# MotorDriver.net
KiCad netlist of a schematic drawn in Altium Designer
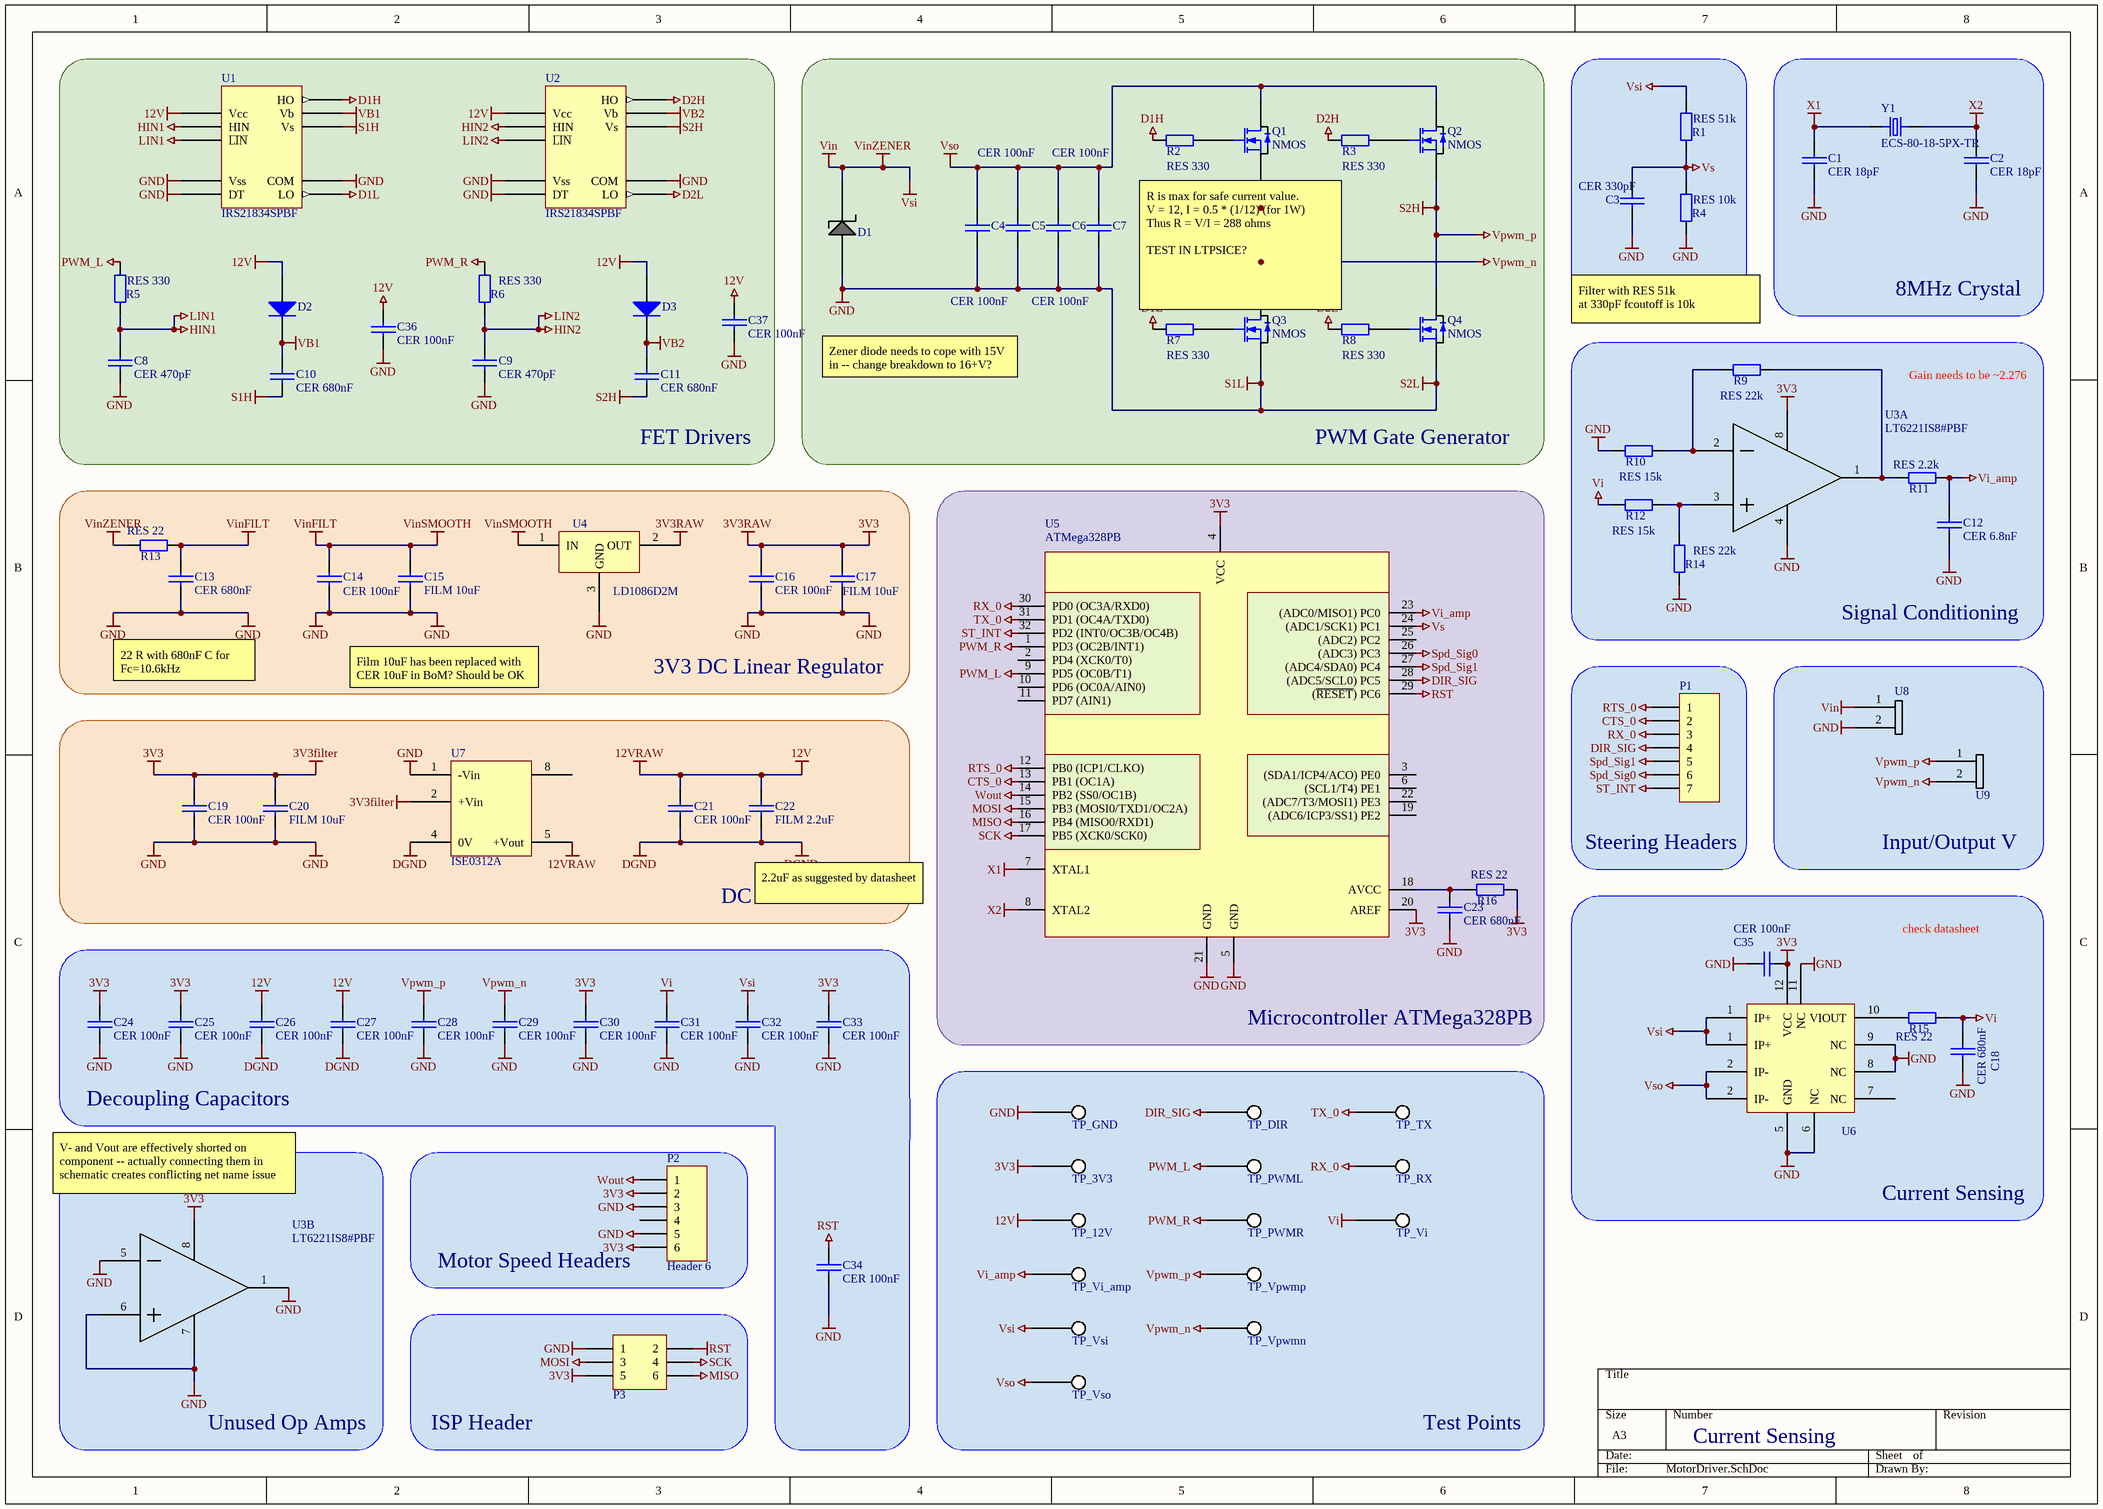
[diagram p0: MotorDriver.SchDoc]

(export (version "E")
  (design (tool "Eeschema 10.0.6"))
  (components
    (comp (ref "C1")
      (value "CER 18pF")
      (footprint "C1210")
      (description "CCAP0805")
      (fields (field (name "MPN") "?"))
      (libsource (lib "E209_Lib") (part "CCAP0805"))
    )
    (comp (ref "C2")
      (value "CER 18pF")
      (footprint "C1210")
      (description "CCAP0805")
      (fields (field (name "MPN") "?"))
      (libsource (lib "E209_Lib") (part "CCAP0805"))
    )
    (comp (ref "C3")
      (value "CER 330pF")
      (footprint "C1206")
      (description "CCAP0805")
      (fields (field (name "MPN") "?"))
      (libsource (lib "E209_Lib") (part "CCAP0805"))
    )
    (comp (ref "C4")
      (value "CER 100nF")
      (footprint "C1206")
      (description "CAP CER 0.1UF 100V C0G 1206")
      (fields (field (name "MPN") "C3216C0G2A104J160AC") (field (name "MANUFACTURER") "TDK Corporation"))
      (libsource (lib "E209_Lib") (part "Cap CER Decoup C3216C0G2A104J160AC"))
    )
    (comp (ref "C5")
      (value "CER 100nF")
      (footprint "C1206")
      (description "CAP CER 0.1UF 100V C0G 1206")
      (fields (field (name "MPN") "C3216C0G2A104J160AC") (field (name "MANUFACTURER") "TDK Corporation"))
      (libsource (lib "E209_Lib") (part "Cap CER Decoup C3216C0G2A104J160AC"))
    )
    (comp (ref "C6")
      (value "CER 100nF")
      (footprint "C1206")
      (description "CAP CER 0.1UF 100V C0G 1206")
      (fields (field (name "MPN") "C3216C0G2A104J160AC") (field (name "MANUFACTURER") "TDK Corporation"))
      (libsource (lib "E209_Lib") (part "Cap CER Decoup C3216C0G2A104J160AC"))
    )
    (comp (ref "C7")
      (value "CER 100nF")
      (footprint "C1206")
      (description "CAP CER 0.1UF 100V C0G 1206")
      (fields (field (name "MPN") "C3216C0G2A104J160AC") (field (name "MANUFACTURER") "TDK Corporation"))
      (libsource (lib "E209_Lib") (part "Cap CER Decoup C3216C0G2A104J160AC"))
    )
    (comp (ref "C8")
      (value "CER 470pF")
      (footprint "C1210")
      (description "CCAP0805")
      (fields (field (name "MPN") "?"))
      (libsource (lib "E209_Lib") (part "CCAP0805"))
    )
    (comp (ref "C9")
      (value "CER 470pF")
      (footprint "C1210")
      (description "CCAP0805")
      (fields (field (name "MPN") "?"))
      (libsource (lib "E209_Lib") (part "CCAP0805"))
    )
    (comp (ref "C10")
      (value "CER 680nF")
      (footprint "C1206")
      (description "CAP CER 0.1UF 100V C0G 1206")
      (fields (field (name "MPN") "C3216C0G2A104J160AC") (field (name "MANUFACTURER") "TDK Corporation"))
      (libsource (lib "E209_Lib") (part "Cap CER Decoup C3216C0G2A104J160AC"))
    )
    (comp (ref "C11")
      (value "CER 680nF")
      (footprint "C1206")
      (description "CAP CER 0.1UF 100V C0G 1206")
      (fields (field (name "MPN") "C3216C0G2A104J160AC") (field (name "MANUFACTURER") "TDK Corporation"))
      (libsource (lib "E209_Lib") (part "Cap CER Decoup C3216C0G2A104J160AC"))
    )
    (comp (ref "C12")
      (value "CER 6.8nF")
      (footprint "C1206")
      (description "CCAP0805")
      (fields (field (name "MPN") "?"))
      (libsource (lib "E209_Lib") (part "CCAP0805"))
    )
    (comp (ref "C13")
      (value "CER 680nF")
      (footprint "C1206")
      (description "CCAP0805")
      (fields (field (name "MPN") "?"))
      (libsource (lib "E209_Lib") (part "CCAP0805"))
    )
    (comp (ref "C14")
      (value "CER 100nF")
      (footprint "C1206")
      (description "CCAP0805")
      (fields (field (name "MPN") "?"))
      (libsource (lib "E209_Lib") (part "CCAP0805"))
    )
    (comp (ref "C15")
      (value "FILM 10uF")
      (footprint "LDECE4150KA0N00")
      (description "CAP FILM 1.5UF 10% 50VDC 2824")
      (fields (field (name "MPN") "LDECE4150KA0N00") (field (name "MANUFACTURER") "KEMET"))
      (libsource (lib "E209_Lib") (part "Cap Film SMD LDECE4150KA0N00"))
    )
    (comp (ref "C16")
      (value "CER 100nF")
      (footprint "C1206")
      (description "CAP CER 0.1UF 100V C0G 1206")
      (fields (field (name "MPN") "C3216C0G2A104J160AC") (field (name "MANUFACTURER") "TDK Corporation"))
      (libsource (lib "E209_Lib") (part "Cap CER Decoup C3216C0G2A104J160AC"))
    )
    (comp (ref "C17")
      (value "FILM 10uF")
      (footprint "LDECE4150KA0N00")
      (description "CAP FILM 1.5UF 10% 50VDC 2824")
      (fields (field (name "MPN") "LDECE4150KA0N00") (field (name "MANUFACTURER") "KEMET"))
      (libsource (lib "E209_Lib") (part "Cap Film SMD LDECE4150KA0N00"))
    )
    (comp (ref "C18")
      (value "CER 680nF")
      (footprint "C1206")
      (description "CCAP0805")
      (fields (field (name "MPN") "?"))
      (libsource (lib "E209_Lib") (part "CCAP0805"))
    )
    (comp (ref "C19")
      (value "CER 100nF")
      (footprint "C1206")
      (description "CCAP0805")
      (fields (field (name "MPN") "?"))
      (libsource (lib "E209_Lib") (part "CCAP0805"))
    )
    (comp (ref "C20")
      (value "FILM 10uF")
      (footprint "LDECE4150KA0N00")
      (description "CAP FILM 1.5UF 10% 50VDC 2824")
      (fields (field (name "MPN") "LDECE4150KA0N00") (field (name "MANUFACTURER") "KEMET"))
      (libsource (lib "E209_Lib") (part "Cap Film SMD LDECE4150KA0N00"))
    )
    (comp (ref "C21")
      (value "CER 100nF")
      (footprint "C1206")
      (description "CCAP0805")
      (fields (field (name "MPN") "?"))
      (libsource (lib "E209_Lib") (part "CCAP0805"))
    )
    (comp (ref "C22")
      (value "FILM 2.2uF")
      (footprint "LDECE4150KA0N00")
      (description "CAP FILM 1.5UF 10% 50VDC 2824")
      (fields (field (name "MPN") "LDECE4150KA0N00") (field (name "MANUFACTURER") "KEMET"))
      (libsource (lib "E209_Lib") (part "Cap Film SMD LDECE4150KA0N00"))
    )
    (comp (ref "C23")
      (value "CER 680nF")
      (footprint "C1206")
      (description "CCAP0805")
      (fields (field (name "MPN") "?"))
      (libsource (lib "E209_Lib") (part "CCAP0805"))
    )
    (comp (ref "C24")
      (value "CER 100nF")
      (footprint "C1206")
      (description "CCAP0805")
      (fields (field (name "MPN") "?"))
      (libsource (lib "E209_Lib") (part "CCAP0805"))
    )
    (comp (ref "C25")
      (value "CER 100nF")
      (footprint "C0805")
      (description "CCAP0805")
      (fields (field (name "MPN") "?"))
      (libsource (lib "E209_Lib") (part "CCAP0805"))
    )
    (comp (ref "C26")
      (value "CER 100nF")
      (footprint "C1206")
      (description "CAP CER 0.1UF 100V C0G 1206")
      (fields (field (name "MPN") "C3216C0G2A104J160AC") (field (name "MANUFACTURER") "TDK Corporation"))
      (libsource (lib "E209_Lib") (part "Cap CER Decoup C3216C0G2A104J160AC"))
    )
    (comp (ref "C27")
      (value "CER 100nF")
      (footprint "C1206")
      (description "CAP CER 0.1UF 100V C0G 1206")
      (fields (field (name "MPN") "C3216C0G2A104J160AC") (field (name "MANUFACTURER") "TDK Corporation"))
      (libsource (lib "E209_Lib") (part "Cap CER Decoup C3216C0G2A104J160AC"))
    )
    (comp (ref "C28")
      (value "CER 100nF")
      (footprint "C1206")
      (description "CCAP0805")
      (fields (field (name "MPN") "?"))
      (libsource (lib "E209_Lib") (part "CCAP0805"))
    )
    (comp (ref "C29")
      (value "CER 100nF")
      (footprint "C1206")
      (description "CCAP0805")
      (fields (field (name "MPN") "?"))
      (libsource (lib "E209_Lib") (part "CCAP0805"))
    )
    (comp (ref "C30")
      (value "CER 100nF")
      (footprint "C0805")
      (description "CCAP0805")
      (fields (field (name "MPN") "?"))
      (libsource (lib "E209_Lib") (part "CCAP0805"))
    )
    (comp (ref "C31")
      (value "CER 100nF")
      (footprint "C0805")
      (description "CCAP0805")
      (fields (field (name "MPN") "?"))
      (libsource (lib "E209_Lib") (part "CCAP0805"))
    )
    (comp (ref "C32")
      (value "CER 100nF")
      (footprint "C1206")
      (description "CCAP0805")
      (fields (field (name "MPN") "?"))
      (libsource (lib "E209_Lib") (part "CCAP0805"))
    )
    (comp (ref "C33")
      (value "CER 100nF")
      (footprint "C0805")
      (description "CCAP0805")
      (fields (field (name "MPN") "?"))
      (libsource (lib "E209_Lib") (part "CCAP0805"))
    )
    (comp (ref "C34")
      (value "CER 100nF")
      (footprint "C1206")
      (description "CCAP0805")
      (fields (field (name "MPN") "?"))
      (libsource (lib "E209_Lib") (part "CCAP0805"))
    )
    (comp (ref "C35")
      (value "CER 100nF")
      (footprint "C1206")
      (description "CCAP0805")
      (fields (field (name "MPN") "?"))
      (libsource (lib "E209_Lib") (part "CCAP0805"))
    )
    (comp (ref "C36")
      (value "CER 100nF")
      (footprint "C1206")
      (description "CAP CER 0.1UF 100V C0G 1206")
      (fields (field (name "MPN") "C3216C0G2A104J160AC") (field (name "MANUFACTURER") "TDK Corporation"))
      (libsource (lib "E209_Lib") (part "Cap CER Decoup C3216C0G2A104J160AC"))
    )
    (comp (ref "C37")
      (value "CER 100nF")
      (footprint "C1206")
      (description "CAP CER 0.1UF 100V C0G 1206")
      (fields (field (name "MPN") "C3216C0G2A104J160AC") (field (name "MANUFACTURER") "TDK Corporation"))
      (libsource (lib "E209_Lib") (part "Cap CER Decoup C3216C0G2A104J160AC"))
    )
    (comp (ref "D1")
      (value "DO-214AA SMB")
      (footprint "DO-214AA")
      (description "14V zener diode")
      (libsource (lib "SumWkshop") (part "SMBJ5351B-TP"))
    )
    (comp (ref "D2")
      (value "MSS1P6-M3/89A")
      (footprint "MicroSMP (DO-219AD)")
      (description "DIODE SCHOTTKY 60V 1A MICROSMP")
      (fields (field (name "MANUFACTURER") "Vishay Semiconductor Diodes Division"))
      (libsource (lib "E209_Lib") (part "Diode MSS1P6-M3/89A"))
    )
    (comp (ref "D3")
      (value "MSS1P6-M3/89A")
      (footprint "MicroSMP (DO-219AD)")
      (description "DIODE SCHOTTKY 60V 1A MICROSMP")
      (fields (field (name "MANUFACTURER") "Vishay Semiconductor Diodes Division"))
      (libsource (lib "E209_Lib") (part "Diode MSS1P6-M3/89A"))
    )
    (comp (ref "P1")
      (value "Header 7")
      (footprint "HDR1X7")
      (description "Header, 7-Pin")
      (fields (field (name "PUBLISHER") "Altium Limited"))
      (libsource (lib "Miscellaneous Connectors") (part "Header 7"))
    )
    (comp (ref "P2")
      (value "Header 6")
      (footprint "HDR1X6")
      (description "Header, 6-Pin")
      (fields (field (name "PUBLISHER") "Altium Limited"))
      (libsource (lib "Miscellaneous Connectors") (part "Header 6"))
    )
    (comp (ref "P3")
      (value "HDR3X2")
      (footprint "HDR2X3_2P54")
      (description "Header, 3-Pin, Dual row")
      (libsource (lib "CommonDevices_V1") (part "HDR3X2"))
    )
    (comp (ref "Q1")
      (value "NMOS")
      (footprint "BSC072N08NS5ATMA1_modified_v2")
      (description "MOSFET N-CH 80V 74A 8TDSON")
      (fields (field (name "MPN") "BSC072N08NS5ATMA1") (field (name "MANUFACTURER") "Infineon Technologies"))
      (libsource (lib "E209_Lib") (part "NMOS OptiMOS BSC072N08NS5ATMA1"))
    )
    (comp (ref "Q2")
      (value "NMOS")
      (footprint "BSC072N08NS5ATMA1_modified_v2")
      (description "MOSFET N-CH 80V 74A 8TDSON")
      (fields (field (name "MPN") "BSC072N08NS5ATMA1") (field (name "MANUFACTURER") "Infineon Technologies"))
      (libsource (lib "E209_Lib") (part "NMOS OptiMOS BSC072N08NS5ATMA1"))
    )
    (comp (ref "Q3")
      (value "NMOS")
      (footprint "BSC072N08NS5ATMA1_modified_v2")
      (description "MOSFET N-CH 80V 74A 8TDSON")
      (fields (field (name "MPN") "BSC072N08NS5ATMA1") (field (name "MANUFACTURER") "Infineon Technologies"))
      (libsource (lib "E209_Lib") (part "NMOS OptiMOS BSC072N08NS5ATMA1"))
    )
    (comp (ref "Q4")
      (value "NMOS")
      (footprint "BSC072N08NS5ATMA1_modified_v2")
      (description "MOSFET N-CH 80V 74A 8TDSON")
      (fields (field (name "MPN") "BSC072N08NS5ATMA1") (field (name "MANUFACTURER") "Infineon Technologies"))
      (libsource (lib "E209_Lib") (part "NMOS OptiMOS BSC072N08NS5ATMA1"))
    )
    (comp (ref "R1")
      (value "RES 51k")
      (footprint "R0805")
      (description "RES0805")
      (fields (field (name "MPN") "?"))
      (libsource (lib "") (part "RES0805_1"))
    )
    (comp (ref "R2")
      (value "RES 330")
      (footprint "R0805")
      (description "RES0805")
      (fields (field (name "MPN") "?"))
      (libsource (lib "E209_Lib") (part "RES0805"))
    )
    (comp (ref "R3")
      (value "RES 330")
      (footprint "R0805")
      (description "RES0805")
      (fields (field (name "MPN") "?"))
      (libsource (lib "E209_Lib") (part "RES0805"))
    )
    (comp (ref "R4")
      (value "RES 10k")
      (footprint "R0805")
      (description "RES0805")
      (fields (field (name "MPN") "?"))
      (libsource (lib "") (part "RES0805_1"))
    )
    (comp (ref "R5")
      (value "RES 330")
      (footprint "R0805")
      (description "RES0805")
      (fields (field (name "MPN") "?"))
      (libsource (lib "") (part "RES0805_1"))
    )
    (comp (ref "R6")
      (value "RES 330")
      (footprint "R0805")
      (description "RES0805")
      (fields (field (name "MPN") "?"))
      (libsource (lib "") (part "RES0805_1"))
    )
    (comp (ref "R7")
      (value "RES 330")
      (footprint "R0805")
      (description "RES0805")
      (fields (field (name "MPN") "?"))
      (libsource (lib "E209_Lib") (part "RES0805"))
    )
    (comp (ref "R8")
      (value "RES 330")
      (footprint "R0805")
      (description "RES0805")
      (fields (field (name "MPN") "?"))
      (libsource (lib "E209_Lib") (part "RES0805"))
    )
    (comp (ref "R9")
      (value "RES 22k")
      (footprint "R0805")
      (description "RES0805")
      (fields (field (name "MPN") "?"))
      (libsource (lib "E209_Lib") (part "RES0805"))
    )
    (comp (ref "R10")
      (value "RES 15k")
      (footprint "R0805")
      (description "RES0805")
      (fields (field (name "MPN") "?"))
      (libsource (lib "E209_Lib") (part "RES0805"))
    )
    (comp (ref "R11")
      (value "RES 2.2k")
      (footprint "R0805")
      (description "RES0805")
      (fields (field (name "MPN") "?"))
      (libsource (lib "") (part "RES0805_2"))
    )
    (comp (ref "R12")
      (value "RES 15k")
      (footprint "R0805")
      (description "RES0805")
      (fields (field (name "MPN") "?"))
      (libsource (lib "E209_Lib") (part "RES0805"))
    )
    (comp (ref "R13")
      (value "RES 22")
      (footprint "R0805")
      (description "RES0805")
      (fields (field (name "MPN") "?"))
      (libsource (lib "E209_Lib") (part "RES0805"))
    )
    (comp (ref "R14")
      (value "RES 22k")
      (footprint "R0805")
      (description "RES0805")
      (fields (field (name "MPN") "?"))
      (libsource (lib "") (part "RES0805_1"))
    )
    (comp (ref "R15")
      (value "RES 22")
      (footprint "R0805")
      (description "RES0805")
      (fields (field (name "MPN") "?"))
      (libsource (lib "E209_Lib") (part "RES0805"))
    )
    (comp (ref "R16")
      (value "RES 22")
      (footprint "R0805")
      (description "RES0805")
      (fields (field (name "MPN") "?"))
      (libsource (lib "E209_Lib") (part "RES0805"))
    )
    (comp (ref "TP_3V3")
      (value "TP_3V3")
      (footprint "TP5015")
      (description "SM Test Point 5015")
      (libsource (lib "SumWkshop") (part "TP_5015"))
    )
    (comp (ref "TP_12V")
      (value "TP_12V")
      (footprint "TP5015")
      (description "SM Test Point 5015")
      (libsource (lib "SumWkshop") (part "TP_5015"))
    )
    (comp (ref "TP_DIR")
      (value "TP_DIR")
      (footprint "TP5015")
      (description "SM Test Point 5015")
      (libsource (lib "SumWkshop") (part "TP_5015"))
    )
    (comp (ref "TP_GND")
      (value "TP_GND")
      (footprint "TP5015")
      (description "SM Test Point 5015")
      (libsource (lib "SumWkshop") (part "TP_5015"))
    )
    (comp (ref "TP_PWML")
      (value "TP_F/B")
      (footprint "TP5015")
      (description "SM Test Point 5015")
      (libsource (lib "SumWkshop") (part "TP_5015"))
    )
    (comp (ref "TP_PWMR")
      (value "TP_PWM")
      (footprint "TP5015")
      (description "SM Test Point 5015")
      (libsource (lib "SumWkshop") (part "TP_5015"))
    )
    (comp (ref "TP_RX")
      (value "TP_RX")
      (footprint "TP5015")
      (description "SM Test Point 5015")
      (libsource (lib "SumWkshop") (part "TP_5015"))
    )
    (comp (ref "TP_TX")
      (value "TP_TX")
      (footprint "TP5015")
      (description "SM Test Point 5015")
      (libsource (lib "SumWkshop") (part "TP_5015"))
    )
    (comp (ref "TP_Vi")
      (value "TP_Vi")
      (footprint "TP5015")
      (description "SM Test Point 5015")
      (libsource (lib "SumWkshop") (part "TP_5015"))
    )
    (comp (ref "TP_Vi_amp")
      (value "TP_Vi_amp")
      (footprint "TP5015")
      (description "SM Test Point 5015")
      (libsource (lib "SumWkshop") (part "TP_5015"))
    )
    (comp (ref "TP_Vpwmn")
      (value "TP_Vsi")
      (footprint "TP5015")
      (description "SM Test Point 5015")
      (libsource (lib "SumWkshop") (part "TP_5015"))
    )
    (comp (ref "TP_Vpwmp")
      (value "TP_Vi_amp")
      (footprint "TP5015")
      (description "SM Test Point 5015")
      (libsource (lib "SumWkshop") (part "TP_5015"))
    )
    (comp (ref "TP_Vsi")
      (value "TP_Vsi")
      (footprint "TP5015")
      (description "SM Test Point 5015")
      (libsource (lib "SumWkshop") (part "TP_5015"))
    )
    (comp (ref "TP_Vso")
      (value "TP_Vso")
      (footprint "TP5015")
      (description "SM Test Point 5015")
      (libsource (lib "SumWkshop") (part "TP_5015"))
    )
    (comp (ref "U1")
      (value "IRS21834SPBF")
      (footprint "SOIC127P600X175-14N")
      (description "IC GATE DRVR HALF-BRIDGE 14SOIC")
      (libsource (lib "SumWkshop") (part "IRS21834SPBF"))
    )
    (comp (ref "U2")
      (value "IRS21834SPBF")
      (footprint "SOIC127P600X175-14N")
      (description "IC GATE DRVR HALF-BRIDGE 14SOIC")
      (libsource (lib "SumWkshop") (part "IRS21834SPBF"))
    )
    (comp (ref "U3")
      (value "LT6221IS8#PBF")
      (footprint "SOIC8_NARROW")
      (libsource (lib "SumWkshop") (part "LT6221IS8#PBF"))
    )
    (comp (ref "U4")
      (value "LD1086D2M")
      (footprint "D2PAK-3L")
      (description "3.3V linear voltage regulator")
      (libsource (lib "SumWkshop") (part "LD1086D2M33TR"))
    )
    (comp (ref "U5")
      (value "ATMega328PB")
      (footprint "TQFP32")
      (description "IC MCU 8BIT 32KB FLASH 32TQFP")
      (libsource (lib "CommonDevices_V1") (part "ATMega328PB"))
    )
    (comp (ref "U6")
      (value "ACS70331EESATR-005U3")
      (footprint "ACS70331_12QFN")
      (description "HIGH SENSITIVITY, 1 MHZ, GMR-BAS")
      (libsource (lib "SumWkshop") (part "ACS70331_QFN"))
    )
    (comp (ref "U7")
      (value "ISE0312A")
      (footprint "ISE0312A")
      (description "3V-12V DC DC converter")
      (libsource (lib "SumWkshop") (part "ISE0312A_8-SMD_5L"))
    )
    (comp (ref "U8")
      (value "2 PIN HEADER 3MM")
      (footprint "3mm_holes")
      (description "3MM HOLES")
      (libsource (lib "SumWkshop") (part "HEADER_2PIN"))
    )
    (comp (ref "U9")
      (value "2 PIN HEADER 3MM")
      (footprint "3mm_holes")
      (description "3MM HOLES")
      (libsource (lib "SumWkshop") (part "HEADER_2PIN"))
    )
    (comp (ref "Y1")
      (value "ECS-80-18-5PX-TR")
      (footprint "XTAL_ECS-80-18-5PX-TR")
      (description "8MHz Â±30ppm Crystal 18pF 60 Ohms HC-49/US")
      (fields (field (name "DIGI-KEY_PART_NUMBER") "XC1271CT-ND") (field (name "MF") "ECS Inc."))
      (libsource (lib "SumWkshop") (part "ECS-80-18-5PX-TR"))
    )
  )
  (nets
    (net (code "1") (name "3V3") (class "Default")
      (node (ref "C16") (pin "2") (pinfunction "2_2") (pintype "passive"))
      (node (ref "C17") (pin "2") (pinfunction "2_2") (pintype "passive"))
      (node (ref "C19") (pin "2") (pinfunction "2_2") (pintype "passive"))
      (node (ref "C20") (pin "2") (pinfunction "2_2") (pintype "passive"))
      (node (ref "C24") (pin "2") (pinfunction "2_2") (pintype "passive"))
      (node (ref "C25") (pin "2") (pinfunction "2_2") (pintype "passive"))
      (node (ref "C30") (pin "2") (pinfunction "2_2") (pintype "passive"))
      (node (ref "C33") (pin "2") (pinfunction "2_2") (pintype "passive"))
      (node (ref "C35") (pin "1") (pinfunction "1_1") (pintype "passive"))
      (node (ref "P2") (pin "2") (pinfunction "2_2") (pintype "passive"))
      (node (ref "P2") (pin "6") (pinfunction "6_6") (pintype "passive"))
      (node (ref "P3") (pin "5") (pinfunction "5_5") (pintype "passive"))
      (node (ref "R16") (pin "2") (pinfunction "2_2") (pintype "passive"))
      (node (ref "TP_3V3") (pin "1") (pinfunction "1_1") (pintype "passive"))
      (node (ref "U3") (pin "8") (pinfunction "8_8") (pintype "passive"))
      (node (ref "U4") (pin "2") (pinfunction "OUT_2") (pintype "passive"))
      (node (ref "U5") (pin "20") (pinfunction "AREF_20") (pintype "passive"))
      (node (ref "U5") (pin "4") (pinfunction "VCC_4") (pintype "passive"))
      (node (ref "U6") (pin "12") (pinfunction "VCC_12") (pintype "passive"))
      (node (ref "U7") (pin "2") (pinfunction "+Vin_2") (pintype "passive"))
    )
    (net (code "2") (name "12V") (class "Default")
      (node (ref "C21") (pin "2") (pinfunction "2_2") (pintype "passive"))
      (node (ref "C22") (pin "2") (pinfunction "2_2") (pintype "passive"))
      (node (ref "C26") (pin "2") (pinfunction "2_2") (pintype "passive"))
      (node (ref "C27") (pin "2") (pinfunction "2_2") (pintype "passive"))
      (node (ref "C36") (pin "2") (pinfunction "2_2") (pintype "passive"))
      (node (ref "C37") (pin "2") (pinfunction "2_2") (pintype "passive"))
      (node (ref "D2") (pin "1") (pinfunction "A_1") (pintype "passive"))
      (node (ref "D3") (pin "1") (pinfunction "A_1") (pintype "passive"))
      (node (ref "TP_12V") (pin "1") (pinfunction "1_1") (pintype "passive"))
      (node (ref "U1") (pin "7") (pinfunction "Vcc_7") (pintype "power_in"))
      (node (ref "U2") (pin "7") (pinfunction "Vcc_7") (pintype "power_in"))
      (node (ref "U7") (pin "5") (pinfunction "+Vout_5") (pintype "passive"))
    )
    (net (code "3") (name "CTS_0") (class "Default")
      (node (ref "P1") (pin "2") (pinfunction "2_2") (pintype "passive"))
      (node (ref "U5") (pin "13") (pinfunction "PB1_(OC1A)_13") (pintype "passive"))
    )
    (net (code "4") (name "D1H") (class "Default")
      (node (ref "R2") (pin "1") (pinfunction "1_1") (pintype "passive"))
      (node (ref "U1") (pin "12") (pinfunction "HO_12") (pintype "output"))
    )
    (net (code "5") (name "D1L") (class "Default")
      (node (ref "R7") (pin "1") (pinfunction "1_1") (pintype "passive"))
      (node (ref "U1") (pin "6") (pinfunction "LO_6") (pintype "output"))
    )
    (net (code "6") (name "D2H") (class "Default")
      (node (ref "R3") (pin "1") (pinfunction "1_1") (pintype "passive"))
      (node (ref "U2") (pin "12") (pinfunction "HO_12") (pintype "output"))
    )
    (net (code "7") (name "D2L") (class "Default")
      (node (ref "R8") (pin "1") (pinfunction "1_1") (pintype "passive"))
      (node (ref "U2") (pin "6") (pinfunction "LO_6") (pintype "output"))
    )
    (net (code "8") (name "DGND") (class "Default")
      (node (ref "C21") (pin "1") (pinfunction "1_1") (pintype "passive"))
      (node (ref "C22") (pin "1") (pinfunction "1_1") (pintype "passive"))
      (node (ref "C26") (pin "1") (pinfunction "1_1") (pintype "passive"))
      (node (ref "C27") (pin "1") (pinfunction "1_1") (pintype "passive"))
      (node (ref "U7") (pin "4") (pinfunction "0V_4") (pintype "passive"))
    )
    (net (code "9") (name "DIR_SIG") (class "Default")
      (node (ref "P1") (pin "4") (pinfunction "4_4") (pintype "passive"))
      (node (ref "TP_DIR") (pin "1") (pinfunction "1_1") (pintype "passive"))
      (node (ref "U5") (pin "28") (pinfunction "(ADC5/SCL0)_PC5_28") (pintype "passive"))
    )
    (net (code "10") (name "GND") (class "Default")
      (node (ref "C1") (pin "1") (pinfunction "1_1") (pintype "passive"))
      (node (ref "C12") (pin "1") (pinfunction "1_1") (pintype "passive"))
      (node (ref "C13") (pin "1") (pinfunction "1_1") (pintype "passive"))
      (node (ref "C14") (pin "1") (pinfunction "1_1") (pintype "passive"))
      (node (ref "C15") (pin "1") (pinfunction "1_1") (pintype "passive"))
      (node (ref "C16") (pin "1") (pinfunction "1_1") (pintype "passive"))
      (node (ref "C17") (pin "1") (pinfunction "1_1") (pintype "passive"))
      (node (ref "C18") (pin "1") (pinfunction "1_1") (pintype "passive"))
      (node (ref "C19") (pin "1") (pinfunction "1_1") (pintype "passive"))
      (node (ref "C2") (pin "1") (pinfunction "1_1") (pintype "passive"))
      (node (ref "C20") (pin "1") (pinfunction "1_1") (pintype "passive"))
      (node (ref "C23") (pin "1") (pinfunction "1_1") (pintype "passive"))
      (node (ref "C24") (pin "1") (pinfunction "1_1") (pintype "passive"))
      (node (ref "C25") (pin "1") (pinfunction "1_1") (pintype "passive"))
      (node (ref "C28") (pin "1") (pinfunction "1_1") (pintype "passive"))
      (node (ref "C29") (pin "1") (pinfunction "1_1") (pintype "passive"))
      (node (ref "C3") (pin "1") (pinfunction "1_1") (pintype "passive"))
      (node (ref "C30") (pin "1") (pinfunction "1_1") (pintype "passive"))
      (node (ref "C31") (pin "1") (pinfunction "1_1") (pintype "passive"))
      (node (ref "C32") (pin "1") (pinfunction "1_1") (pintype "passive"))
      (node (ref "C33") (pin "1") (pinfunction "1_1") (pintype "passive"))
      (node (ref "C34") (pin "1") (pinfunction "1_1") (pintype "passive"))
      (node (ref "C35") (pin "2") (pinfunction "2_2") (pintype "passive"))
      (node (ref "C36") (pin "1") (pinfunction "1_1") (pintype "passive"))
      (node (ref "C37") (pin "1") (pinfunction "1_1") (pintype "passive"))
      (node (ref "C4") (pin "1") (pinfunction "1_1") (pintype "passive"))
      (node (ref "C5") (pin "1") (pinfunction "1_1") (pintype "passive"))
      (node (ref "C6") (pin "1") (pinfunction "1_1") (pintype "passive"))
      (node (ref "C7") (pin "1") (pinfunction "1_1") (pintype "passive"))
      (node (ref "C8") (pin "1") (pinfunction "1_1") (pintype "passive"))
      (node (ref "C9") (pin "1") (pinfunction "1_1") (pintype "passive"))
      (node (ref "D1") (pin "2") (pinfunction "2_2") (pintype "passive"))
      (node (ref "P2") (pin "3") (pinfunction "3_3") (pintype "passive"))
      (node (ref "P2") (pin "5") (pinfunction "5_5") (pintype "passive"))
      (node (ref "P3") (pin "1") (pinfunction "1_1") (pintype "passive"))
      (node (ref "Q3") (pin "1") (pinfunction "S_1") (pintype "passive"))
      (node (ref "Q4") (pin "1") (pinfunction "S_1") (pintype "passive"))
      (node (ref "R10") (pin "1") (pinfunction "1_1") (pintype "passive"))
      (node (ref "R14") (pin "1") (pinfunction "1_1") (pintype "passive"))
      (node (ref "R4") (pin "1") (pinfunction "1_1") (pintype "passive"))
      (node (ref "TP_GND") (pin "1") (pinfunction "1_1") (pintype "passive"))
      (node (ref "U1") (pin "3") (pinfunction "Vss_3") (pintype "power_in"))
      (node (ref "U1") (pin "4") (pinfunction "DT_4") (pintype "passive"))
      (node (ref "U1") (pin "5") (pinfunction "COM_5") (pintype "power_in"))
      (node (ref "U2") (pin "3") (pinfunction "Vss_3") (pintype "power_in"))
      (node (ref "U2") (pin "4") (pinfunction "DT_4") (pintype "passive"))
      (node (ref "U2") (pin "5") (pinfunction "COM_5") (pintype "power_in"))
      (node (ref "U3") (pin "1") (pinfunction "1_1") (pintype "passive"))
      (node (ref "U3") (pin "4") (pinfunction "4_4") (pintype "passive"))
      (node (ref "U3") (pin "5") (pinfunction "5_5") (pintype "passive"))
      (node (ref "U3") (pin "6") (pinfunction "6_6") (pintype "passive"))
      (node (ref "U3") (pin "7") (pinfunction "7_7") (pintype "passive"))
      (node (ref "U4") (pin "3") (pinfunction "GND_3") (pintype "passive"))
      (node (ref "U5") (pin "21") (pinfunction "GND_21") (pintype "passive"))
      (node (ref "U5") (pin "5") (pinfunction "GND_5") (pintype "passive"))
      (node (ref "U6") (pin "11") (pinfunction "NC_11") (pintype "passive"))
      (node (ref "U6") (pin "5") (pinfunction "GND_5") (pintype "passive"))
      (node (ref "U6") (pin "6") (pinfunction "NC_6") (pintype "passive"))
      (node (ref "U6") (pin "8") (pinfunction "NC_8") (pintype "passive"))
      (node (ref "U6") (pin "9") (pinfunction "NC_9") (pintype "passive"))
      (node (ref "U7") (pin "1") (pinfunction "-Vin_1") (pintype "passive"))
      (node (ref "U8") (pin "2") (pinfunction "2_2") (pintype "passive"))
    )
    (net (code "11") (name "HIN1") (class "Default")
      (node (ref "C8") (pin "2") (pinfunction "2_2") (pintype "passive"))
      (node (ref "R5") (pin "1") (pinfunction "1_1") (pintype "passive"))
      (node (ref "U1") (pin "1") (pinfunction "HIN_1") (pintype "passive"))
      (node (ref "U1") (pin "2") (pinfunction "L̅I̅N̅_2") (pintype "passive"))
    )
    (net (code "12") (name "HIN2") (class "Default")
      (node (ref "C9") (pin "2") (pinfunction "2_2") (pintype "passive"))
      (node (ref "R6") (pin "1") (pinfunction "1_1") (pintype "passive"))
      (node (ref "U2") (pin "1") (pinfunction "HIN_1") (pintype "passive"))
      (node (ref "U2") (pin "2") (pinfunction "L̅I̅N̅_2") (pintype "passive"))
    )
    (net (code "13") (name "MISO") (class "Default")
      (node (ref "P3") (pin "6") (pinfunction "6_6") (pintype "passive"))
      (node (ref "U5") (pin "16") (pinfunction "PB4_(MISO0/RXD1)_16") (pintype "passive"))
    )
    (net (code "14") (name "MOSI") (class "Default")
      (node (ref "P3") (pin "3") (pinfunction "3_3") (pintype "passive"))
      (node (ref "U5") (pin "15") (pinfunction "PB3_(MOSI0/TXD1/OC2A)_15") (pintype "passive"))
    )
    (net (code "15") (name "Net-(Q1-G)") (class "Default")
      (node (ref "Q1") (pin "4") (pinfunction "G_4") (pintype "passive"))
      (node (ref "R2") (pin "2") (pinfunction "2_2") (pintype "passive"))
    )
    (net (code "16") (name "Net-(Q2-G)") (class "Default")
      (node (ref "Q2") (pin "4") (pinfunction "G_4") (pintype "passive"))
      (node (ref "R3") (pin "2") (pinfunction "2_2") (pintype "passive"))
    )
    (net (code "17") (name "Net-(Q3-G)") (class "Default")
      (node (ref "Q3") (pin "4") (pinfunction "G_4") (pintype "passive"))
      (node (ref "R7") (pin "2") (pinfunction "2_2") (pintype "passive"))
    )
    (net (code "18") (name "Net-(Q4-G)") (class "Default")
      (node (ref "Q4") (pin "4") (pinfunction "G_4") (pintype "passive"))
      (node (ref "R8") (pin "2") (pinfunction "2_2") (pintype "passive"))
    )
    (net (code "19") (name "Net-(R10-Pad2)") (class "Default")
      (node (ref "R10") (pin "2") (pinfunction "2_2") (pintype "passive"))
      (node (ref "R9") (pin "1") (pinfunction "1_1") (pintype "passive"))
      (node (ref "U3") (pin "2") (pinfunction "2_2") (pintype "passive"))
    )
    (net (code "20") (name "Net-(R11-Pad2)") (class "Default")
      (node (ref "R11") (pin "2") (pinfunction "2_2") (pintype "passive"))
      (node (ref "R9") (pin "2") (pinfunction "2_2") (pintype "passive"))
      (node (ref "U3") (pin "1") (pinfunction "1_1") (pintype "passive"))
    )
    (net (code "21") (name "Net-(R12-Pad2)") (class "Default")
      (node (ref "R12") (pin "2") (pinfunction "2_2") (pintype "passive"))
      (node (ref "R14") (pin "2") (pinfunction "2_2") (pintype "passive"))
      (node (ref "U3") (pin "3") (pinfunction "3_3") (pintype "passive"))
    )
    (net (code "22") (name "Net-(U5-AVCC)") (class "Default")
      (node (ref "C23") (pin "2") (pinfunction "2_2") (pintype "passive"))
      (node (ref "R16") (pin "1") (pinfunction "1_1") (pintype "passive"))
      (node (ref "U5") (pin "18") (pinfunction "AVCC_18") (pintype "passive"))
    )
    (net (code "23") (name "Net-(U6-VIOUT)") (class "Default")
      (node (ref "R15") (pin "1") (pinfunction "1_1") (pintype "passive"))
      (node (ref "U6") (pin "10") (pinfunction "VIOUT_10") (pintype "passive"))
    )
    (net (code "24") (name "PWM_L") (class "Default")
      (node (ref "R5") (pin "2") (pinfunction "2_2") (pintype "passive"))
      (node (ref "TP_PWML") (pin "1") (pinfunction "1_1") (pintype "passive"))
      (node (ref "U5") (pin "9") (pinfunction "PD5_(OC0B/T1)_9") (pintype "passive"))
    )
    (net (code "25") (name "PWM_R") (class "Default")
      (node (ref "R6") (pin "2") (pinfunction "2_2") (pintype "passive"))
      (node (ref "TP_PWMR") (pin "1") (pinfunction "1_1") (pintype "passive"))
      (node (ref "U5") (pin "1") (pinfunction "PD3_(OC2B/INT1)_1") (pintype "passive"))
    )
    (net (code "26") (name "RST") (class "Default")
      (node (ref "C34") (pin "2") (pinfunction "2_2") (pintype "passive"))
      (node (ref "P3") (pin "2") (pinfunction "2_2") (pintype "passive"))
      (node (ref "U5") (pin "29") (pinfunction "(~{RESET})_PC6_29") (pintype "passive"))
    )
    (net (code "27") (name "RTS_0") (class "Default")
      (node (ref "P1") (pin "1") (pinfunction "1_1") (pintype "passive"))
      (node (ref "U5") (pin "12") (pinfunction "PB0_(ICP1/CLKO)_12") (pintype "passive"))
    )
    (net (code "28") (name "RX_0") (class "Default")
      (node (ref "P1") (pin "3") (pinfunction "3_3") (pintype "passive"))
      (node (ref "TP_RX") (pin "1") (pinfunction "1_1") (pintype "passive"))
      (node (ref "U5") (pin "30") (pinfunction "PD0_(OC3A/RXD0)_30") (pintype "passive"))
    )
    (net (code "29") (name "S1H") (class "Default")
      (node (ref "C10") (pin "1") (pinfunction "1_1") (pintype "passive"))
      (node (ref "C29") (pin "2") (pinfunction "2_2") (pintype "passive"))
      (node (ref "Q1") (pin "1") (pinfunction "S_1") (pintype "passive"))
      (node (ref "Q3") (pin "8") (pinfunction "D_8") (pintype "passive"))
      (node (ref "TP_Vpwmn") (pin "1") (pinfunction "1_1") (pintype "passive"))
      (node (ref "U1") (pin "11") (pinfunction "Vs_11") (pintype "power_in"))
      (node (ref "U9") (pin "2") (pinfunction "2_2") (pintype "passive"))
    )
    (net (code "30") (name "S2H") (class "Default")
      (node (ref "C11") (pin "1") (pinfunction "1_1") (pintype "passive"))
      (node (ref "C28") (pin "2") (pinfunction "2_2") (pintype "passive"))
      (node (ref "Q2") (pin "1") (pinfunction "S_1") (pintype "passive"))
      (node (ref "Q4") (pin "8") (pinfunction "D_8") (pintype "passive"))
      (node (ref "TP_Vpwmp") (pin "1") (pinfunction "1_1") (pintype "passive"))
      (node (ref "U2") (pin "11") (pinfunction "Vs_11") (pintype "power_in"))
      (node (ref "U9") (pin "1") (pinfunction "1_1") (pintype "passive"))
    )
    (net (code "31") (name "SCK") (class "Default")
      (node (ref "P3") (pin "4") (pinfunction "4_4") (pintype "passive"))
      (node (ref "U5") (pin "17") (pinfunction "PB5_(XCK0/SCK0)_17") (pintype "passive"))
    )
    (net (code "32") (name "ST_INT") (class "Default")
      (node (ref "P1") (pin "7") (pinfunction "7_7") (pintype "passive"))
      (node (ref "U5") (pin "32") (pinfunction "PD2_(INT0/OC3B/OC4B)_32") (pintype "passive"))
    )
    (net (code "33") (name "Spd_Sig0") (class "Default")
      (node (ref "P1") (pin "6") (pinfunction "6_6") (pintype "passive"))
      (node (ref "U5") (pin "26") (pinfunction "(ADC3)_PC3_26") (pintype "passive"))
    )
    (net (code "34") (name "Spd_Sig1") (class "Default")
      (node (ref "P1") (pin "5") (pinfunction "5_5") (pintype "passive"))
      (node (ref "U5") (pin "27") (pinfunction "(ADC4/SDA0)_PC4_27") (pintype "passive"))
    )
    (net (code "35") (name "TX_0") (class "Default")
      (node (ref "TP_TX") (pin "1") (pinfunction "1_1") (pintype "passive"))
      (node (ref "U5") (pin "31") (pinfunction "PD1_(OC4A/TXD0)_31") (pintype "passive"))
    )
    (net (code "36") (name "VB1") (class "Default")
      (node (ref "C10") (pin "2") (pinfunction "2_2") (pintype "passive"))
      (node (ref "D2") (pin "2") (pinfunction "K_2") (pintype "passive"))
      (node (ref "U1") (pin "13") (pinfunction "Vb_13") (pintype "power_in"))
    )
    (net (code "37") (name "VB2") (class "Default")
      (node (ref "C11") (pin "2") (pinfunction "2_2") (pintype "passive"))
      (node (ref "D3") (pin "2") (pinfunction "K_2") (pintype "passive"))
      (node (ref "U2") (pin "13") (pinfunction "Vb_13") (pintype "power_in"))
    )
    (net (code "38") (name "Vi") (class "Default")
      (node (ref "C18") (pin "2") (pinfunction "2_2") (pintype "passive"))
      (node (ref "C31") (pin "2") (pinfunction "2_2") (pintype "passive"))
      (node (ref "R12") (pin "1") (pinfunction "1_1") (pintype "passive"))
      (node (ref "R15") (pin "2") (pinfunction "2_2") (pintype "passive"))
      (node (ref "TP_Vi") (pin "1") (pinfunction "1_1") (pintype "passive"))
    )
    (net (code "39") (name "Vi_amp") (class "Default")
      (node (ref "C12") (pin "2") (pinfunction "2_2") (pintype "passive"))
      (node (ref "R11") (pin "1") (pinfunction "1_1") (pintype "passive"))
      (node (ref "TP_Vi_amp") (pin "1") (pinfunction "1_1") (pintype "passive"))
      (node (ref "U5") (pin "23") (pinfunction "(ADC0/MISO1)_PC0_23") (pintype "passive"))
    )
    (net (code "40") (name "Vin") (class "Default")
      (node (ref "C32") (pin "2") (pinfunction "2_2") (pintype "passive"))
      (node (ref "D1") (pin "1") (pinfunction "1_1") (pintype "passive"))
      (node (ref "R1") (pin "2") (pinfunction "2_2") (pintype "passive"))
      (node (ref "R13") (pin "1") (pinfunction "1_1") (pintype "passive"))
      (node (ref "TP_Vsi") (pin "1") (pinfunction "1_1") (pintype "passive"))
      (node (ref "U6") (pin "1") (pinfunction "IP+_1") (pintype "passive"))
      (node (ref "U8") (pin "1") (pinfunction "1_1") (pintype "passive"))
    )
    (net (code "41") (name "VinFILT") (class "Default")
      (node (ref "C13") (pin "2") (pinfunction "2_2") (pintype "passive"))
      (node (ref "C14") (pin "2") (pinfunction "2_2") (pintype "passive"))
      (node (ref "C15") (pin "2") (pinfunction "2_2") (pintype "passive"))
      (node (ref "R13") (pin "2") (pinfunction "2_2") (pintype "passive"))
      (node (ref "U4") (pin "1") (pinfunction "IN_1") (pintype "passive"))
    )
    (net (code "42") (name "Vs") (class "Default")
      (node (ref "C3") (pin "2") (pinfunction "2_2") (pintype "passive"))
      (node (ref "R1") (pin "1") (pinfunction "1_1") (pintype "passive"))
      (node (ref "R4") (pin "2") (pinfunction "2_2") (pintype "passive"))
      (node (ref "U5") (pin "24") (pinfunction "(ADC1/SCK1)_PC1_24") (pintype "passive"))
    )
    (net (code "43") (name "Vso") (class "Default")
      (node (ref "C4") (pin "2") (pinfunction "2_2") (pintype "passive"))
      (node (ref "C5") (pin "2") (pinfunction "2_2") (pintype "passive"))
      (node (ref "C6") (pin "2") (pinfunction "2_2") (pintype "passive"))
      (node (ref "C7") (pin "2") (pinfunction "2_2") (pintype "passive"))
      (node (ref "Q1") (pin "8") (pinfunction "D_8") (pintype "passive"))
      (node (ref "Q2") (pin "8") (pinfunction "D_8") (pintype "passive"))
      (node (ref "TP_Vso") (pin "1") (pinfunction "1_1") (pintype "passive"))
      (node (ref "U6") (pin "2") (pinfunction "IP-_2") (pintype "passive"))
    )
    (net (code "44") (name "Wout") (class "Default")
      (node (ref "P2") (pin "1") (pinfunction "1_1") (pintype "passive"))
      (node (ref "U5") (pin "14") (pinfunction "PB2_(SS0/OC1B)_14") (pintype "passive"))
    )
    (net (code "45") (name "X1") (class "Default")
      (node (ref "C1") (pin "2") (pinfunction "2_2") (pintype "passive"))
      (node (ref "U5") (pin "7") (pinfunction "XTAL1_7") (pintype "passive"))
      (node (ref "Y1") (pin "1") (pinfunction "1_1") (pintype "passive"))
    )
    (net (code "46") (name "X2") (class "Default")
      (node (ref "C2") (pin "2") (pinfunction "2_2") (pintype "passive"))
      (node (ref "U5") (pin "8") (pinfunction "XTAL2_8") (pintype "passive"))
      (node (ref "Y1") (pin "2") (pinfunction "2_2") (pintype "passive"))
    )
    (net (code "47") (name "unconnected-(P2-Pad4)") (class "Default")
      (node (ref "P2") (pin "4") (pinfunction "4_4") (pintype "passive"))
    )
    (net (code "48") (name "unconnected-(U5-(ADC2)_PC2-Pad25)") (class "Default")
      (node (ref "U5") (pin "25") (pinfunction "(ADC2)_PC2_25") (pintype "passive"))
    )
    (net (code "49") (name "unconnected-(U5-(ADC6{slash}ICP3{slash}SS1)_PE2-Pad19)") (class "Default")
      (node (ref "U5") (pin "19") (pinfunction "(ADC6/ICP3/SS1)_PE2_19") (pintype "passive"))
    )
    (net (code "50") (name "unconnected-(U5-(ADC7{slash}T3{slash}MOSI1)_PE3-Pad22)") (class "Default")
      (node (ref "U5") (pin "22") (pinfunction "(ADC7/T3/MOSI1)_PE3_22") (pintype "passive"))
    )
    (net (code "51") (name "unconnected-(U5-(SCL1{slash}T4)_PE1-Pad6)") (class "Default")
      (node (ref "U5") (pin "6") (pinfunction "(SCL1/T4)_PE1_6") (pintype "passive"))
    )
    (net (code "52") (name "unconnected-(U5-(SDA1{slash}ICP4{slash}ACO)_PE0-Pad3)") (class "Default")
      (node (ref "U5") (pin "3") (pinfunction "(SDA1/ICP4/ACO)_PE0_3") (pintype "passive"))
    )
    (net (code "53") (name "unconnected-(U5-PD4_(XCK0{slash}T0)-Pad2)") (class "Default")
      (node (ref "U5") (pin "2") (pinfunction "PD4_(XCK0/T0)_2") (pintype "passive"))
    )
    (net (code "54") (name "unconnected-(U5-PD6_(OC0A{slash}AIN0)-Pad10)") (class "Default")
      (node (ref "U5") (pin "10") (pinfunction "PD6_(OC0A/AIN0)_10") (pintype "passive"))
    )
    (net (code "55") (name "unconnected-(U5-PD7_(AIN1)-Pad11)") (class "Default")
      (node (ref "U5") (pin "11") (pinfunction "PD7_(AIN1)_11") (pintype "passive"))
    )
    (net (code "56") (name "unconnected-(U6-NC-Pad7)") (class "Default")
      (node (ref "U6") (pin "7") (pinfunction "NC_7") (pintype "passive"))
    )
    (net (code "57") (name "unconnected-(U7-Pad8)") (class "Default")
      (node (ref "U7") (pin "8") (pintype "passive"))
    )
  )
)
